# hv_mux_tr_sw.net
KiCad netlist of a schematic drawn in Altium Designer
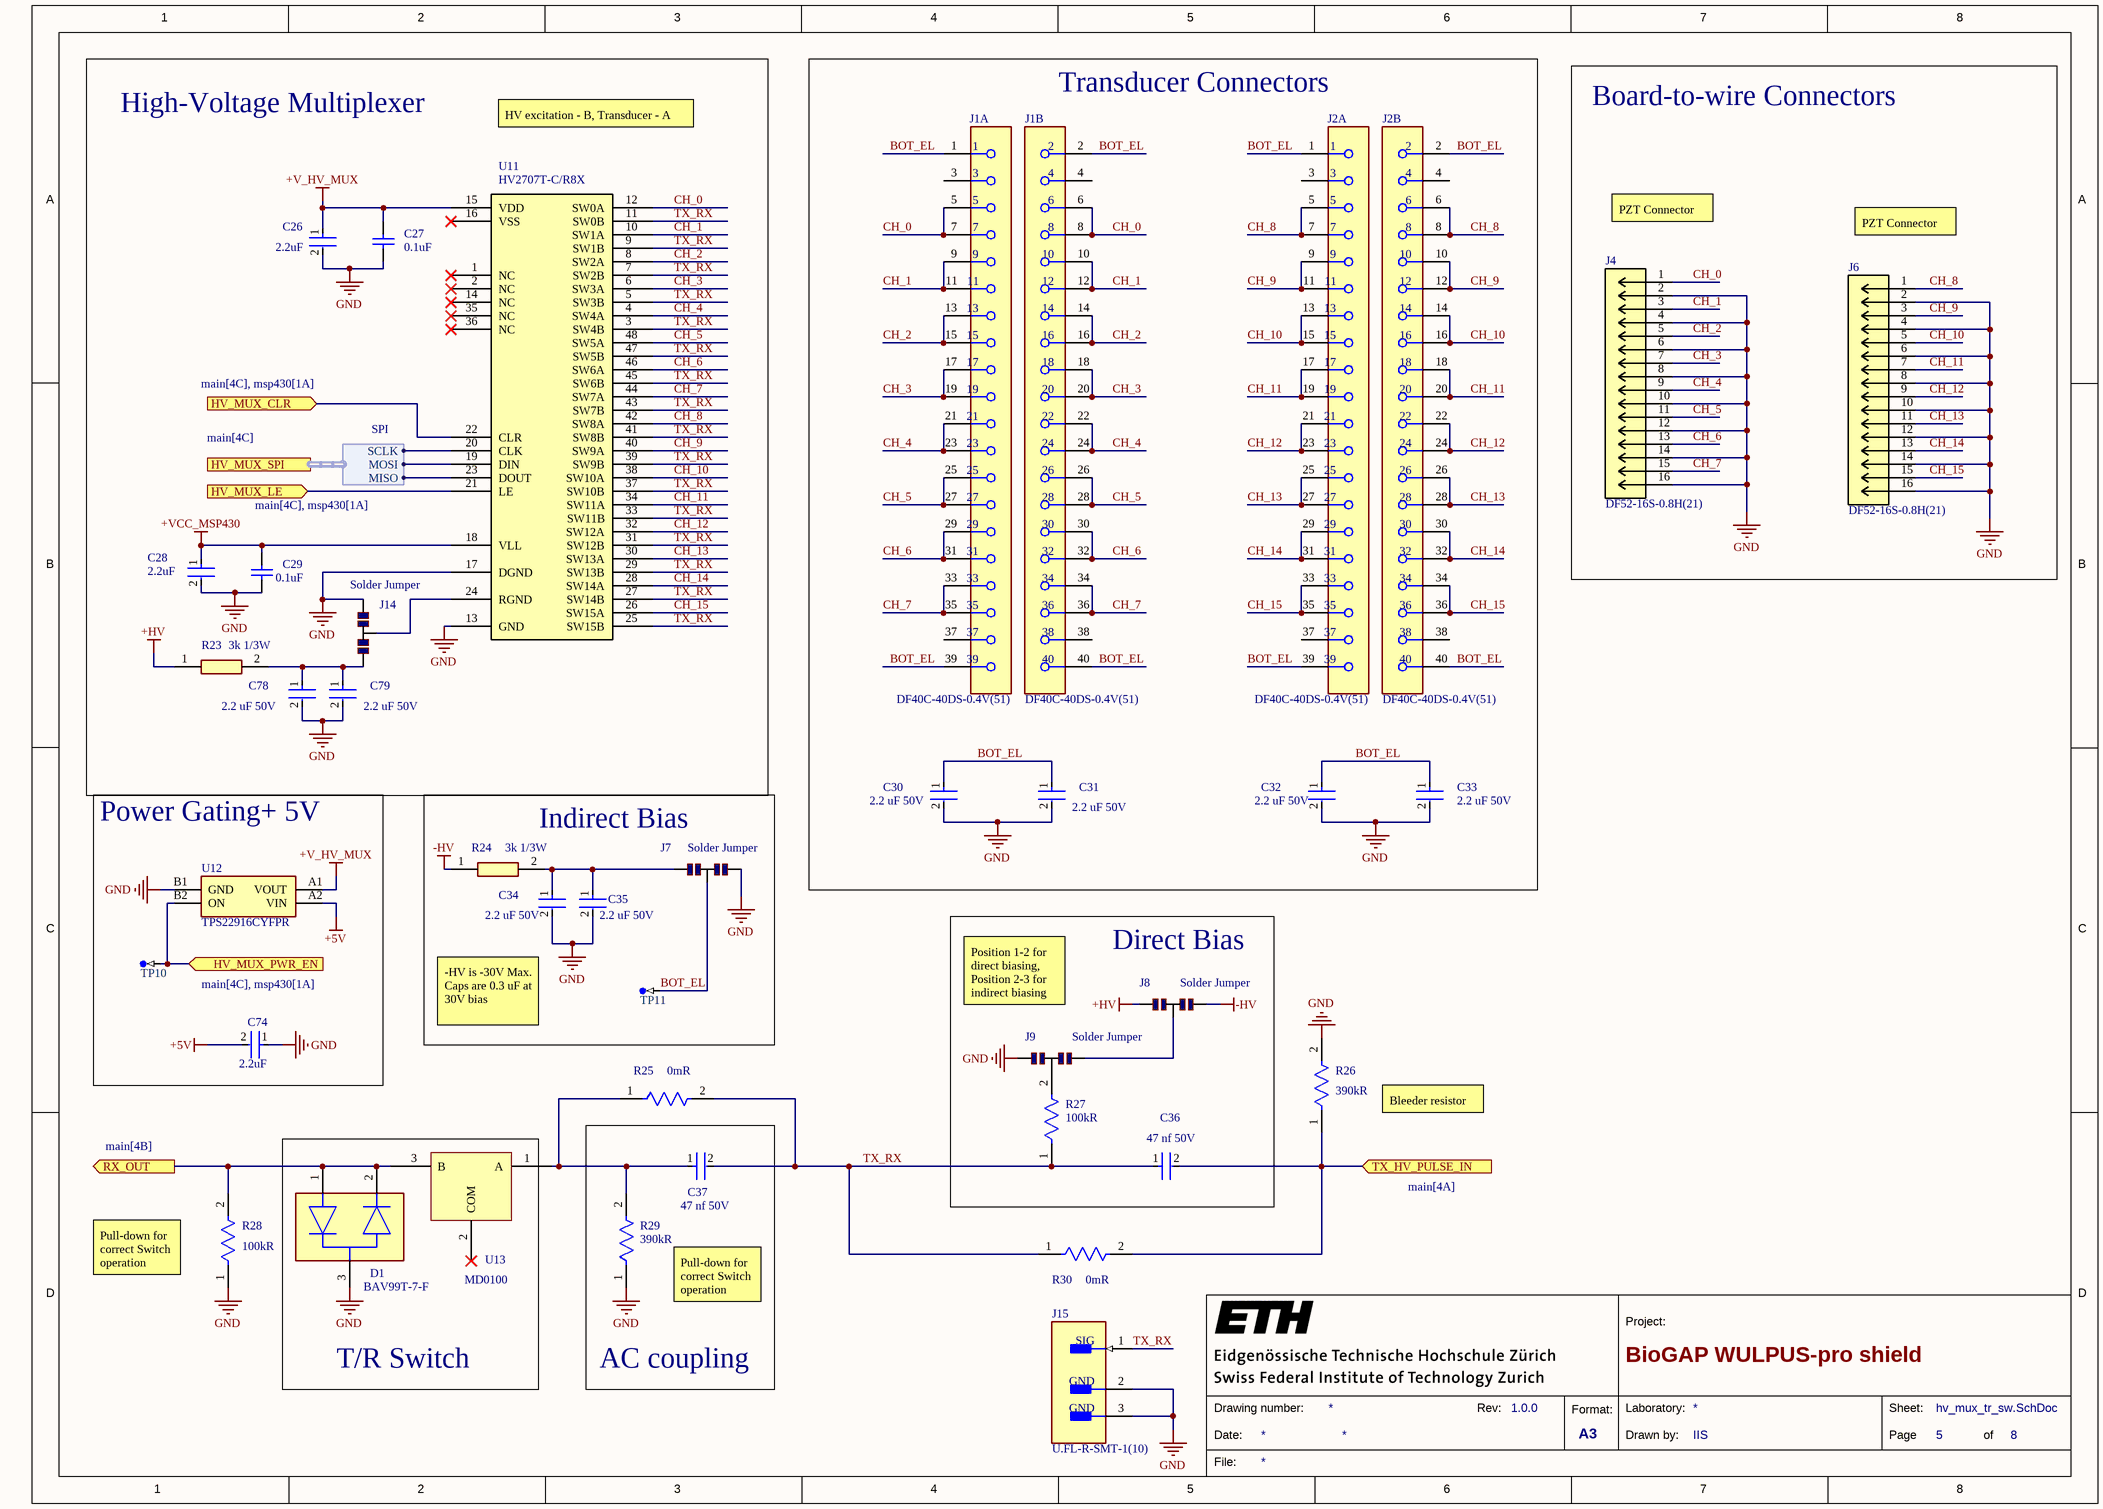
[diagram p0: hv_mux_tr_sw.SchDoc]

(export (version "E")
  (design (tool "Eeschema 10.0.6"))
  (components
    (comp (ref "C26")
      (value "C1005X7S1A225K050BC")
      (footprint "FP-C1005-050-0_15-0_1-MFG")
      (fields (field (name "CAPACITANCE") "2.2uF") (field (name "TOLERANCE") "10%"))
      (libsource (lib "Altium Content Vault") (part "b4654b650e69147ec39a6b967a45e02"))
    )
    (comp (ref "C27")
      (value "C0402C104K4RACTU")
      (footprint "CAPC1005X55X30LL05T10")
      (fields (field (name "MANUFACTURER") "Kemet") (field (name "CAPACITANCE") "0.1uF"))
      (libsource (lib "Altium Content Vault") (part "CAP"))
    )
    (comp (ref "C28")
      (value "C1005X7S1A225K050BC")
      (footprint "FP-C1005-050-0_15-0_1-MFG")
      (fields (field (name "CAPACITANCE") "2.2uF") (field (name "TOLERANCE") "10%"))
      (libsource (lib "Altium Content Vault") (part "b4654b650e69147ec39a6b967a45e02"))
    )
    (comp (ref "C29")
      (value "C0402C104K4RACTU")
      (footprint "CAPC1005X55X30LL05T10")
      (fields (field (name "MANUFACTURER") "Kemet") (field (name "CAPACITANCE") "0.1uF"))
      (libsource (lib "Altium Content Vault") (part "CAP"))
    )
    (comp (ref "C30")
      (value "GRM188R61H225ME11")
      (footprint "FP-GRM188-0_2-IPC_B")
      (fields (field (name "CAPACITANCE") "2.2 uF 50V") (field (name "TOLERANCE") "20%"))
      (libsource (lib "Altium Content Vault") (part "11868f565c42a9108669ba33697ecf6"))
    )
    (comp (ref "C31")
      (value "GRM188R61H225ME11")
      (footprint "FP-GRM188-0_2-IPC_B")
      (fields (field (name "CAPACITANCE") "2.2 uF 50V") (field (name "TOLERANCE") "20%"))
      (libsource (lib "Altium Content Vault") (part "11868f565c42a9108669ba33697ecf6"))
    )
    (comp (ref "C32")
      (value "GRM188R61H225ME11")
      (footprint "FP-GRM188-0_2-IPC_B")
      (fields (field (name "CAPACITANCE") "2.2 uF 50V") (field (name "TOLERANCE") "20%"))
      (libsource (lib "Altium Content Vault") (part "11868f565c42a9108669ba33697ecf6"))
    )
    (comp (ref "C33")
      (value "GRM188R61H225ME11")
      (footprint "FP-GRM188-0_2-IPC_B")
      (fields (field (name "CAPACITANCE") "2.2 uF 50V") (field (name "TOLERANCE") "20%"))
      (libsource (lib "Altium Content Vault") (part "11868f565c42a9108669ba33697ecf6"))
    )
    (comp (ref "C34")
      (value "GRM188R61H225ME11")
      (footprint "FP-GRM188-0_2-IPC_B")
      (fields (field (name "CAPACITANCE") "2.2 uF 50V") (field (name "TOLERANCE") "20%"))
      (libsource (lib "Altium Content Vault") (part "11868f565c42a9108669ba33697ecf6"))
    )
    (comp (ref "C35")
      (value "GRM188R61H225ME11")
      (footprint "FP-GRM188-0_2-IPC_B")
      (fields (field (name "CAPACITANCE") "2.2 uF 50V") (field (name "TOLERANCE") "20%"))
      (libsource (lib "Altium Content Vault") (part "11868f565c42a9108669ba33697ecf6"))
    )
    (comp (ref "C36")
      (value "GRM155R71H473ME14D")
      (footprint "FP-GRM155-0_05-IPC_C")
      (fields (field (name "TOLERANCE") "20%") (field (name "CAPACITANCE") "47 nf 50V"))
      (libsource (lib "Altium Content Vault") (part "02cd4be3c70576c341d710602a673aa"))
    )
    (comp (ref "C37")
      (value "GRM155R71H473ME14D")
      (footprint "FP-GRM155-0_05-IPC_C")
      (fields (field (name "TOLERANCE") "20%") (field (name "CAPACITANCE") "47 nf 50V"))
      (libsource (lib "Altium Content Vault") (part "02cd4be3c70576c341d710602a673aa"))
    )
    (comp (ref "C74")
      (value "C1005X7S1A225K050BC")
      (footprint "FP-C1005-050-0_15-0_1-MFG")
      (fields (field (name "CAPACITANCE") "2.2uF") (field (name "TOLERANCE") "10%"))
      (libsource (lib "Altium Content Vault") (part "b4654b650e69147ec39a6b967a45e02"))
    )
    (comp (ref "C78")
      (value "GRM188R61H225ME11")
      (footprint "FP-GRM188-0_2-IPC_B")
      (fields (field (name "CAPACITANCE") "2.2 uF 50V") (field (name "TOLERANCE") "20%"))
      (libsource (lib "Altium Content Vault") (part "11868f565c42a9108669ba33697ecf6"))
    )
    (comp (ref "C79")
      (value "GRM188R61H225ME11")
      (footprint "FP-GRM188-0_2-IPC_B")
      (fields (field (name "CAPACITANCE") "2.2 uF 50V") (field (name "TOLERANCE") "20%"))
      (libsource (lib "Altium Content Vault") (part "11868f565c42a9108669ba33697ecf6"))
    )
    (comp (ref "D1")
      (value "BAV99T-7-F")
      (footprint "FP-SOT523-MFG")
      (description "DIODE ARRAY GP 85V 75MA SOT523")
      (fields
        (field (name "OCTOPART") "https://octopart.com/bav99t-7-f-diodes+inc.-326340")
        (field (name "MANUFACTURER") "Diodes Inc.")
      )
      (libsource (lib "Altium Content Vault") (part "070e4dda4d860bc04de3109e77921ad"))
    )
    (comp (ref "J1")
      (value "DF40C-40DS-0.4V(51)")
      (footprint "FP-DF40C-40DS-0_4V_51-MFG")
      (description "CONN RCPT 40POS SMD GOLD")
      (fields
        (field (name "MANUFACTURER") "Hirose")
        (field (name "OCTOPART") "https://octopart.com/df40c-40ds-0.4v%2851%29-hirose-19073526")
      )
      (libsource (lib "Altium Content Vault") (part "7acf1c4a8db21028d11741a46a6ec78"))
    )
    (comp (ref "J2")
      (value "DF40C-40DS-0.4V(51)")
      (footprint "FP-DF40C-40DS-0_4V_51-MFG")
      (description "CONN RCPT 40POS SMD GOLD")
      (fields
        (field (name "MANUFACTURER") "Hirose")
        (field (name "OCTOPART") "https://octopart.com/df40c-40ds-0.4v%2851%29-hirose-19073526")
      )
      (libsource (lib "Altium Content Vault") (part "7acf1c4a8db21028d11741a46a6ec78"))
    )
    (comp (ref "J4")
      (value "DF52-16S-0.8H(21)")
      (footprint "CONN_DF52-16S-0.8H(21)_HIR")
      (description "No Description Available")
      (fields (field (name "COPYRIGHT") "Copyright (C) 2022 Ultra Librarian. All rights reserved."))
      (libsource (lib "wulpus_hv") (part "DF52-16S-0.8H(21)"))
    )
    (comp (ref "J6")
      (value "DF52-16S-0.8H(21)")
      (footprint "CONN_DF52-16S-0.8H(21)_HIR")
      (description "No Description Available")
      (fields (field (name "COPYRIGHT") "Copyright (C) 2022 Ultra Librarian. All rights reserved."))
      (libsource (lib "wulpus_hv") (part "DF52-16S-0.8H(21)"))
    )
    (comp (ref "J7")
      (value "Solder Jumper")
      (footprint "Jumper 3 pins")
      (description "Solder Jumper 3 Pads")
      (libsource (lib "ETHZ Vault") (part "Solder Jumper 3-pads"))
    )
    (comp (ref "J8")
      (value "Solder Jumper")
      (footprint "Jumper 3 pins")
      (description "Solder Jumper 3 Pads")
      (libsource (lib "ETHZ Vault") (part "Solder Jumper 3-pads"))
    )
    (comp (ref "J9")
      (value "Solder Jumper")
      (footprint "Jumper 3 pins")
      (description "Solder Jumper 3 Pads")
      (libsource (lib "ETHZ Vault") (part "Solder Jumper 3-pads"))
    )
    (comp (ref "J14")
      (value "Solder Jumper")
      (footprint "Jumper 3 pins")
      (description "Solder Jumper 3 Pads")
      (libsource (lib "wulpus_pro_acq_pcb") (part "CMP-00467-6"))
    )
    (comp (ref "J15")
      (value "U.FL-R-SMT-1(10)")
      (footprint "FP-U_FL-R-SMT-1_10-MFG")
      (description "CONN U.FL RCPT STR 50 OHM SMD")
      (libsource (lib "Altium Content Vault") (part "7158abf7d987fa84906f6fb0d115710"))
    )
    (comp (ref "R23")
      (value "ERJ-PA3J302V")
      (footprint "SamacSys:ERJP03_PA3_(0603)")
      (description "Resistor")
      (fields (field (name "MOUSER PART NUMBER") "667-ERJ-PA3J302V") (field (name "RES") "3k 1/3W"))
      (libsource (lib "*") (part "ERJ-PA3J302V"))
    )
    (comp (ref "R24")
      (value "ERJ-PA3J302V")
      (footprint "SamacSys:ERJP03_PA3_(0603)")
      (fields (field (name "MOUSER PART NUMBER") "667-ERJ-PA3J302V") (field (name "RES") "3k 1/3W"))
      (libsource (lib "*") (part "ERJ-PA3J302V"))
    )
    (comp (ref "R25")
      (value "CRCW04020000Z0ED")
      (footprint "FP-CRCW0402-e3-IPC_C")
      (fields (field (name "TOLERANCE") "5%") (field (name "RESISTANCE") "0mR"))
      (libsource (lib "Altium Content Vault") (part "1029c3af85768c4190bb7ad29bc67b5"))
    )
    (comp (ref "R26")
      (value "RC1005F394CS")
      (footprint "FP-RC1005-MFG")
      (fields (field (name "TOLERANCE") "1%") (field (name "RESISTANCE") "390kR"))
      (libsource (lib "Altium Content Vault") (part "1029c3af85768c4190bb7ad29bc67b5"))
    )
    (comp (ref "R27")
      (value "ERJ-2RKF1003X")
      (footprint "FP-ERJ2RK-IPC_C")
      (fields (field (name "RESISTANCE") "100kR") (field (name "TOLERANCE") "1%"))
      (libsource (lib "Altium Content Vault") (part "1029c3af85768c4190bb7ad29bc67b5"))
    )
    (comp (ref "R28")
      (value "ERJ-2RKF1003X")
      (footprint "FP-ERJ2RK-IPC_C")
      (fields (field (name "RESISTANCE") "100kR") (field (name "TOLERANCE") "1%"))
      (libsource (lib "Altium Content Vault") (part "1029c3af85768c4190bb7ad29bc67b5"))
    )
    (comp (ref "R29")
      (value "RC1005F394CS")
      (footprint "FP-RC1005-MFG")
      (fields (field (name "TOLERANCE") "1%") (field (name "RESISTANCE") "390kR"))
      (libsource (lib "Altium Content Vault") (part "1029c3af85768c4190bb7ad29bc67b5"))
    )
    (comp (ref "R30")
      (value "CRCW04020000Z0ED")
      (footprint "FP-CRCW0402-e3-IPC_C")
      (fields (field (name "TOLERANCE") "5%") (field (name "RESISTANCE") "0mR"))
      (libsource (lib "Altium Content Vault") (part "1029c3af85768c4190bb7ad29bc67b5"))
    )
    (comp (ref "TP10")
      (value "TP-SM-C-100")
      (footprint "TP-SM-C-100")
      (description "Test Point, Surface Mount, Circular, Pad Diameter 1 mm")
      (libsource (lib "wulpus") (part "CMP-0484-00002-1"))
    )
    (comp (ref "TP11")
      (value "TP-SM-C-100")
      (footprint "TP-SM-C-100")
      (description "Test Point, Surface Mount, Circular, Pad Diameter 1 mm")
      (libsource (lib "wulpus") (part "CMP-0484-00002-1"))
    )
    (comp (ref "U11")
      (value "HV2707T-C/R8X")
      (footprint "LQFP48_7X7MC_MCH")
      (description "16-CH 200V No Hv Bias Switch (SPST), 2 Bleed Resistor 48 LQFP 7X7X1.4MM T/r Rohs Compliant: Yes")
      (fields
        (field (name "MANUFACTURER") "Microchip")
        (field (name "MANUFACTURER PART NUMBER") "HV2707T-C/R8X")
      )
      (libsource (lib "wulpus_hv") (part "HV2707T-C/R8X"))
    )
    (comp (ref "U12")
      (value "TPS22916CYFPR")
      (footprint "BGA4C40P2X2_78X78X50")
      (description "TPS22916 5.5-V, 2-A Ultra-Low Leakage Load Switch")
      (libsource (lib "TPS22916CYFPR") (part "TPS22916CYFPR"))
    )
    (comp (ref "U13") (value "MD0100") (footprint "AMP_PHA-1+") (libsource (lib "MD01000") (part "MD0100")))
  )
  (nets
    (net (code "2") (name "+5V") (class "Default")
      (node (ref "C74") (pin "2") (pinfunction "2_2") (pintype "passive"))
      (node (ref "U12") (pin "A2") (pinfunction "VIN_A2") (pintype "passive"))
    )
    (net (code "3") (name "+HV") (class "Default")
      (node (ref "J8") (pin "1") (pinfunction "1_1") (pintype "passive"))
      (node (ref "R23") (pin "1") (pinfunction "1_1") (pintype "passive"))
    )
    (net (code "4") (name "+VCC_MSP430") (class "Default")
      (node (ref "C28") (pin "1") (pinfunction "1_1") (pintype "passive"))
      (node (ref "C29") (pin "2") (pinfunction "2_2") (pintype "passive"))
      (node (ref "U11") (pin "18") (pinfunction "VLL_18") (pintype "passive"))
    )
    (net (code "5") (name "+V_HV_MUX") (class "Default")
      (node (ref "C26") (pin "1") (pinfunction "1_1") (pintype "passive"))
      (node (ref "C27") (pin "2") (pinfunction "2_2") (pintype "passive"))
      (node (ref "U11") (pin "15") (pinfunction "VDD_15") (pintype "passive"))
      (node (ref "U12") (pin "A1") (pinfunction "VOUT_A1") (pintype "passive"))
    )
    (net (code "6") (name "-HV") (class "Default")
      (node (ref "J8") (pin "3") (pinfunction "3_3") (pintype "passive"))
      (node (ref "R24") (pin "1") (pinfunction "1_1") (pintype "passive"))
    )
    (net (code "7") (name "/BOT_EL") (class "Default")
      (node (ref "C30") (pin "1") (pinfunction "1_1") (pintype "passive"))
      (node (ref "C31") (pin "1") (pinfunction "1_1") (pintype "passive"))
      (node (ref "C32") (pin "1") (pinfunction "1_1") (pintype "passive"))
      (node (ref "C33") (pin "1") (pinfunction "1_1") (pintype "passive"))
      (node (ref "J1") (pin "1") (pinfunction "1_1") (pintype "passive"))
      (node (ref "J1") (pin "2") (pinfunction "2_2") (pintype "passive"))
      (node (ref "J1") (pin "39") (pinfunction "39_39") (pintype "passive"))
      (node (ref "J1") (pin "40") (pinfunction "40_40") (pintype "passive"))
      (node (ref "J2") (pin "1") (pinfunction "1_1") (pintype "passive"))
      (node (ref "J2") (pin "2") (pinfunction "2_2") (pintype "passive"))
      (node (ref "J2") (pin "39") (pinfunction "39_39") (pintype "passive"))
      (node (ref "J2") (pin "40") (pinfunction "40_40") (pintype "passive"))
      (node (ref "J7") (pin "2") (pinfunction "2_2") (pintype "passive"))
      (node (ref "TP11") (pin "1") (pinfunction "1_1") (pintype "input"))
    )
    (net (code "8") (name "/CH_0") (class "Default")
      (node (ref "J1") (pin "5") (pinfunction "5_5") (pintype "passive"))
      (node (ref "J1") (pin "6") (pinfunction "6_6") (pintype "passive"))
      (node (ref "J1") (pin "7") (pinfunction "7_7") (pintype "passive"))
      (node (ref "J1") (pin "8") (pinfunction "8_8") (pintype "passive"))
      (node (ref "J4") (pin "1") (pinfunction "1_1") (pintype "passive"))
      (node (ref "U11") (pin "12") (pinfunction "SW0A_12") (pintype "passive"))
    )
    (net (code "9") (name "/CH_1") (class "Default")
      (node (ref "J1") (pin "10") (pinfunction "10_10") (pintype "passive"))
      (node (ref "J1") (pin "11") (pinfunction "11_11") (pintype "passive"))
      (node (ref "J1") (pin "12") (pinfunction "12_12") (pintype "passive"))
      (node (ref "J1") (pin "9") (pinfunction "9_9") (pintype "passive"))
      (node (ref "J4") (pin "3") (pinfunction "3_3") (pintype "passive"))
      (node (ref "U11") (pin "10") (pinfunction "SW1A_10") (pintype "passive"))
    )
    (net (code "10") (name "/CH_2") (class "Default")
      (node (ref "J1") (pin "13") (pinfunction "13_13") (pintype "passive"))
      (node (ref "J1") (pin "14") (pinfunction "14_14") (pintype "passive"))
      (node (ref "J1") (pin "15") (pinfunction "15_15") (pintype "passive"))
      (node (ref "J1") (pin "16") (pinfunction "16_16") (pintype "passive"))
      (node (ref "J4") (pin "5") (pinfunction "5_5") (pintype "passive"))
      (node (ref "U11") (pin "8") (pinfunction "SW2A_8") (pintype "passive"))
    )
    (net (code "11") (name "/CH_3") (class "Default")
      (node (ref "J1") (pin "17") (pinfunction "17_17") (pintype "passive"))
      (node (ref "J1") (pin "18") (pinfunction "18_18") (pintype "passive"))
      (node (ref "J1") (pin "19") (pinfunction "19_19") (pintype "passive"))
      (node (ref "J1") (pin "20") (pinfunction "20_20") (pintype "passive"))
      (node (ref "J4") (pin "7") (pinfunction "7_7") (pintype "passive"))
      (node (ref "U11") (pin "6") (pinfunction "SW3A_6") (pintype "passive"))
    )
    (net (code "12") (name "/CH_4") (class "Default")
      (node (ref "J1") (pin "21") (pinfunction "21_21") (pintype "passive"))
      (node (ref "J1") (pin "22") (pinfunction "22_22") (pintype "passive"))
      (node (ref "J1") (pin "23") (pinfunction "23_23") (pintype "passive"))
      (node (ref "J1") (pin "24") (pinfunction "24_24") (pintype "passive"))
      (node (ref "J4") (pin "9") (pinfunction "9_9") (pintype "passive"))
      (node (ref "U11") (pin "4") (pinfunction "SW4A_4") (pintype "passive"))
    )
    (net (code "13") (name "/CH_5") (class "Default")
      (node (ref "J1") (pin "25") (pinfunction "25_25") (pintype "passive"))
      (node (ref "J1") (pin "26") (pinfunction "26_26") (pintype "passive"))
      (node (ref "J1") (pin "27") (pinfunction "27_27") (pintype "passive"))
      (node (ref "J1") (pin "28") (pinfunction "28_28") (pintype "passive"))
      (node (ref "J4") (pin "11") (pinfunction "11_11") (pintype "passive"))
      (node (ref "U11") (pin "48") (pinfunction "SW5A_48") (pintype "passive"))
    )
    (net (code "14") (name "/CH_6") (class "Default")
      (node (ref "J1") (pin "29") (pinfunction "29_29") (pintype "passive"))
      (node (ref "J1") (pin "30") (pinfunction "30_30") (pintype "passive"))
      (node (ref "J1") (pin "31") (pinfunction "31_31") (pintype "passive"))
      (node (ref "J1") (pin "32") (pinfunction "32_32") (pintype "passive"))
      (node (ref "J4") (pin "13") (pinfunction "13_13") (pintype "passive"))
      (node (ref "U11") (pin "46") (pinfunction "SW6A_46") (pintype "passive"))
    )
    (net (code "15") (name "/CH_7") (class "Default")
      (node (ref "J1") (pin "33") (pinfunction "33_33") (pintype "passive"))
      (node (ref "J1") (pin "34") (pinfunction "34_34") (pintype "passive"))
      (node (ref "J1") (pin "35") (pinfunction "35_35") (pintype "passive"))
      (node (ref "J1") (pin "36") (pinfunction "36_36") (pintype "passive"))
      (node (ref "J4") (pin "15") (pinfunction "15_15") (pintype "passive"))
      (node (ref "U11") (pin "44") (pinfunction "SW7A_44") (pintype "passive"))
    )
    (net (code "16") (name "/CH_8") (class "Default")
      (node (ref "J2") (pin "5") (pinfunction "5_5") (pintype "passive"))
      (node (ref "J2") (pin "6") (pinfunction "6_6") (pintype "passive"))
      (node (ref "J2") (pin "7") (pinfunction "7_7") (pintype "passive"))
      (node (ref "J2") (pin "8") (pinfunction "8_8") (pintype "passive"))
      (node (ref "J6") (pin "1") (pinfunction "1_1") (pintype "passive"))
      (node (ref "U11") (pin "42") (pinfunction "SW8A_42") (pintype "passive"))
    )
    (net (code "17") (name "/CH_9") (class "Default")
      (node (ref "J2") (pin "10") (pinfunction "10_10") (pintype "passive"))
      (node (ref "J2") (pin "11") (pinfunction "11_11") (pintype "passive"))
      (node (ref "J2") (pin "12") (pinfunction "12_12") (pintype "passive"))
      (node (ref "J2") (pin "9") (pinfunction "9_9") (pintype "passive"))
      (node (ref "J6") (pin "3") (pinfunction "3_3") (pintype "passive"))
      (node (ref "U11") (pin "40") (pinfunction "SW9A_40") (pintype "passive"))
    )
    (net (code "18") (name "/CH_10") (class "Default")
      (node (ref "J2") (pin "13") (pinfunction "13_13") (pintype "passive"))
      (node (ref "J2") (pin "14") (pinfunction "14_14") (pintype "passive"))
      (node (ref "J2") (pin "15") (pinfunction "15_15") (pintype "passive"))
      (node (ref "J2") (pin "16") (pinfunction "16_16") (pintype "passive"))
      (node (ref "J6") (pin "5") (pinfunction "5_5") (pintype "passive"))
      (node (ref "U11") (pin "38") (pinfunction "SW10A_38") (pintype "passive"))
    )
    (net (code "19") (name "/CH_11") (class "Default")
      (node (ref "J2") (pin "17") (pinfunction "17_17") (pintype "passive"))
      (node (ref "J2") (pin "18") (pinfunction "18_18") (pintype "passive"))
      (node (ref "J2") (pin "19") (pinfunction "19_19") (pintype "passive"))
      (node (ref "J2") (pin "20") (pinfunction "20_20") (pintype "passive"))
      (node (ref "J6") (pin "7") (pinfunction "7_7") (pintype "passive"))
      (node (ref "U11") (pin "34") (pinfunction "SW11A_34") (pintype "passive"))
    )
    (net (code "20") (name "/CH_12") (class "Default")
      (node (ref "J2") (pin "21") (pinfunction "21_21") (pintype "passive"))
      (node (ref "J2") (pin "22") (pinfunction "22_22") (pintype "passive"))
      (node (ref "J2") (pin "23") (pinfunction "23_23") (pintype "passive"))
      (node (ref "J2") (pin "24") (pinfunction "24_24") (pintype "passive"))
      (node (ref "J6") (pin "9") (pinfunction "9_9") (pintype "passive"))
      (node (ref "U11") (pin "32") (pinfunction "SW12A_32") (pintype "passive"))
    )
    (net (code "21") (name "/CH_13") (class "Default")
      (node (ref "J2") (pin "25") (pinfunction "25_25") (pintype "passive"))
      (node (ref "J2") (pin "26") (pinfunction "26_26") (pintype "passive"))
      (node (ref "J2") (pin "27") (pinfunction "27_27") (pintype "passive"))
      (node (ref "J2") (pin "28") (pinfunction "28_28") (pintype "passive"))
      (node (ref "J6") (pin "11") (pinfunction "11_11") (pintype "passive"))
      (node (ref "U11") (pin "30") (pinfunction "SW13A_30") (pintype "passive"))
    )
    (net (code "22") (name "/CH_14") (class "Default")
      (node (ref "J2") (pin "29") (pinfunction "29_29") (pintype "passive"))
      (node (ref "J2") (pin "30") (pinfunction "30_30") (pintype "passive"))
      (node (ref "J2") (pin "31") (pinfunction "31_31") (pintype "passive"))
      (node (ref "J2") (pin "32") (pinfunction "32_32") (pintype "passive"))
      (node (ref "J6") (pin "13") (pinfunction "13_13") (pintype "passive"))
      (node (ref "U11") (pin "28") (pinfunction "SW14A_28") (pintype "passive"))
    )
    (net (code "23") (name "/CH_15") (class "Default")
      (node (ref "J2") (pin "33") (pinfunction "33_33") (pintype "passive"))
      (node (ref "J2") (pin "34") (pinfunction "34_34") (pintype "passive"))
      (node (ref "J2") (pin "35") (pinfunction "35_35") (pintype "passive"))
      (node (ref "J2") (pin "36") (pinfunction "36_36") (pintype "passive"))
      (node (ref "J6") (pin "15") (pinfunction "15_15") (pintype "passive"))
      (node (ref "U11") (pin "26") (pinfunction "SW15A_26") (pintype "passive"))
    )
    (net (code "24") (name "/HV_MUX_CLR") (class "Default")
      (node (ref "U11") (pin "22") (pinfunction "CLR_22") (pintype "passive"))
    )
    (net (code "25") (name "/HV_MUX_LE") (class "Default")
      (node (ref "U11") (pin "21") (pinfunction "LE_21") (pintype "passive"))
    )
    (net (code "26") (name "/HV_MUX_PWR_EN") (class "Default")
      (node (ref "TP10") (pin "1") (pinfunction "1_1") (pintype "input"))
      (node (ref "U12") (pin "B2") (pinfunction "ON_B2") (pintype "passive"))
    )
    (net (code "27") (name "/MISO") (class "Default")
      (node (ref "U11") (pin "23") (pinfunction "DOUT_23") (pintype "passive"))
    )
    (net (code "28") (name "/MOSI") (class "Default")
      (node (ref "U11") (pin "19") (pinfunction "DIN_19") (pintype "passive"))
    )
    (net (code "29") (name "/RX_OUT") (class "Default")
      (node (ref "D1") (pin "1") (pinfunction "1_1") (pintype "passive"))
      (node (ref "D1") (pin "2") (pinfunction "2_2") (pintype "passive"))
      (node (ref "R28") (pin "2") (pinfunction "2_2") (pintype "passive"))
      (node (ref "U13") (pin "3") (pinfunction "B_3") (pintype "passive"))
    )
    (net (code "30") (name "/SCLK") (class "Default")
      (node (ref "U11") (pin "20") (pinfunction "CLK_20") (pintype "passive"))
    )
    (net (code "31") (name "/TX_HV_PULSE_IN") (class "Default")
      (node (ref "C36") (pin "2") (pinfunction "2_2") (pintype "passive"))
      (node (ref "R26") (pin "1") (pinfunction "1_1") (pintype "passive"))
      (node (ref "R30") (pin "2") (pinfunction "2_2") (pintype "passive"))
    )
    (net (code "32") (name "/TX_RX") (class "Default")
      (node (ref "C36") (pin "1") (pinfunction "1_1") (pintype "passive"))
      (node (ref "C37") (pin "2") (pinfunction "2_2") (pintype "passive"))
      (node (ref "J15") (pin "1") (pinfunction "SIG_1") (pintype "input"))
      (node (ref "R25") (pin "2") (pinfunction "2_2") (pintype "passive"))
      (node (ref "R27") (pin "1") (pinfunction "1_1") (pintype "passive"))
      (node (ref "R30") (pin "1") (pinfunction "1_1") (pintype "passive"))
      (node (ref "U11") (pin "11") (pinfunction "SW0B_11") (pintype "passive"))
      (node (ref "U11") (pin "25") (pinfunction "SW15B_25") (pintype "passive"))
      (node (ref "U11") (pin "27") (pinfunction "SW14B_27") (pintype "passive"))
      (node (ref "U11") (pin "29") (pinfunction "SW13B_29") (pintype "passive"))
      (node (ref "U11") (pin "3") (pinfunction "SW4B_3") (pintype "passive"))
      (node (ref "U11") (pin "31") (pinfunction "SW12B_31") (pintype "passive"))
      (node (ref "U11") (pin "33") (pinfunction "SW11B_33") (pintype "passive"))
      (node (ref "U11") (pin "37") (pinfunction "SW10B_37") (pintype "passive"))
      (node (ref "U11") (pin "39") (pinfunction "SW9B_39") (pintype "passive"))
      (node (ref "U11") (pin "41") (pinfunction "SW8B_41") (pintype "passive"))
      (node (ref "U11") (pin "43") (pinfunction "SW7B_43") (pintype "passive"))
      (node (ref "U11") (pin "45") (pinfunction "SW6B_45") (pintype "passive"))
      (node (ref "U11") (pin "47") (pinfunction "SW5B_47") (pintype "passive"))
      (node (ref "U11") (pin "5") (pinfunction "SW3B_5") (pintype "passive"))
      (node (ref "U11") (pin "7") (pinfunction "SW2B_7") (pintype "passive"))
      (node (ref "U11") (pin "9") (pinfunction "SW1B_9") (pintype "passive"))
    )
    (net (code "34") (name "GND") (class "Default")
      (node (ref "C26") (pin "2") (pinfunction "2_2") (pintype "passive"))
      (node (ref "C27") (pin "1") (pinfunction "1_1") (pintype "passive"))
      (node (ref "C28") (pin "2") (pinfunction "2_2") (pintype "passive"))
      (node (ref "C29") (pin "1") (pinfunction "1_1") (pintype "passive"))
      (node (ref "C30") (pin "2") (pinfunction "2_2") (pintype "passive"))
      (node (ref "C31") (pin "2") (pinfunction "2_2") (pintype "passive"))
      (node (ref "C32") (pin "2") (pinfunction "2_2") (pintype "passive"))
      (node (ref "C33") (pin "2") (pinfunction "2_2") (pintype "passive"))
      (node (ref "C34") (pin "2") (pinfunction "2_2") (pintype "passive"))
      (node (ref "C35") (pin "2") (pinfunction "2_2") (pintype "passive"))
      (node (ref "C74") (pin "1") (pinfunction "1_1") (pintype "passive"))
      (node (ref "C78") (pin "2") (pinfunction "2_2") (pintype "passive"))
      (node (ref "C79") (pin "2") (pinfunction "2_2") (pintype "passive"))
      (node (ref "D1") (pin "3") (pinfunction "3_3") (pintype "passive"))
      (node (ref "J14") (pin "3") (pinfunction "3_3") (pintype "passive"))
      (node (ref "J15") (pin "2") (pinfunction "GND_2") (pintype "power_in"))
      (node (ref "J15") (pin "3") (pinfunction "GND_3") (pintype "power_in"))
      (node (ref "J4") (pin "10") (pinfunction "10_10") (pintype "passive"))
      (node (ref "J4") (pin "12") (pinfunction "12_12") (pintype "passive"))
      (node (ref "J4") (pin "14") (pinfunction "14_14") (pintype "passive"))
      (node (ref "J4") (pin "16") (pinfunction "16_16") (pintype "passive"))
      (node (ref "J4") (pin "2") (pinfunction "2_2") (pintype "passive"))
      (node (ref "J4") (pin "4") (pinfunction "4_4") (pintype "passive"))
      (node (ref "J4") (pin "6") (pinfunction "6_6") (pintype "passive"))
      (node (ref "J4") (pin "8") (pinfunction "8_8") (pintype "passive"))
      (node (ref "J6") (pin "10") (pinfunction "10_10") (pintype "passive"))
      (node (ref "J6") (pin "12") (pinfunction "12_12") (pintype "passive"))
      (node (ref "J6") (pin "14") (pinfunction "14_14") (pintype "passive"))
      (node (ref "J6") (pin "16") (pinfunction "16_16") (pintype "passive"))
      (node (ref "J6") (pin "2") (pinfunction "2_2") (pintype "passive"))
      (node (ref "J6") (pin "4") (pinfunction "4_4") (pintype "passive"))
      (node (ref "J6") (pin "6") (pinfunction "6_6") (pintype "passive"))
      (node (ref "J6") (pin "8") (pinfunction "8_8") (pintype "passive"))
      (node (ref "J7") (pin "3") (pinfunction "3_3") (pintype "passive"))
      (node (ref "J9") (pin "1") (pinfunction "1_1") (pintype "passive"))
      (node (ref "R26") (pin "2") (pinfunction "2_2") (pintype "passive"))
      (node (ref "R28") (pin "1") (pinfunction "1_1") (pintype "passive"))
      (node (ref "R29") (pin "1") (pinfunction "1_1") (pintype "passive"))
      (node (ref "U11") (pin "13") (pinfunction "GND_13") (pintype "passive"))
      (node (ref "U11") (pin "17") (pinfunction "DGND_17") (pintype "passive"))
      (node (ref "U12") (pin "B1") (pinfunction "GND_B1") (pintype "passive"))
    )
    (net (code "35") (name "Net-(C34-Pad1)") (class "Default")
      (node (ref "C34") (pin "1") (pinfunction "1_1") (pintype "passive"))
      (node (ref "C35") (pin "1") (pinfunction "1_1") (pintype "passive"))
      (node (ref "J7") (pin "1") (pinfunction "1_1") (pintype "passive"))
      (node (ref "R24") (pin "2") (pinfunction "2_2") (pintype "passive"))
    )
    (net (code "36") (name "Net-(C78-Pad1)") (class "Default")
      (node (ref "C78") (pin "1") (pinfunction "1_1") (pintype "passive"))
      (node (ref "C79") (pin "1") (pinfunction "1_1") (pintype "passive"))
      (node (ref "J14") (pin "1") (pinfunction "1_1") (pintype "passive"))
      (node (ref "R23") (pin "2") (pinfunction "2_2") (pintype "passive"))
    )
    (net (code "37") (name "Net-(J8-Pad2)") (class "Default")
      (node (ref "J8") (pin "2") (pinfunction "2_2") (pintype "passive"))
      (node (ref "J9") (pin "3") (pinfunction "3_3") (pintype "passive"))
    )
    (net (code "38") (name "Net-(J9-Pad2)") (class "Default")
      (node (ref "J9") (pin "2") (pinfunction "2_2") (pintype "passive"))
      (node (ref "R27") (pin "2") (pinfunction "2_2") (pintype "passive"))
    )
    (net (code "39") (name "Net-(U11-RGND)") (class "Default")
      (node (ref "J14") (pin "2") (pinfunction "2_2") (pintype "passive"))
      (node (ref "U11") (pin "24") (pinfunction "RGND_24") (pintype "passive"))
    )
    (net (code "40") (name "Net-(U13-A)") (class "Default")
      (node (ref "C37") (pin "1") (pinfunction "1_1") (pintype "passive"))
      (node (ref "R25") (pin "1") (pinfunction "1_1") (pintype "passive"))
      (node (ref "R29") (pin "2") (pinfunction "2_2") (pintype "passive"))
      (node (ref "U13") (pin "1") (pinfunction "A_1") (pintype "passive"))
    )
    (net (code "41") (name "unconnected-(J1-Pad3)") (class "Default")
      (node (ref "J1") (pin "3") (pinfunction "3_3") (pintype "passive"))
    )
    (net (code "42") (name "unconnected-(J1-Pad4)") (class "Default")
      (node (ref "J1") (pin "4") (pinfunction "4_4") (pintype "passive"))
    )
    (net (code "43") (name "unconnected-(J1-Pad37)") (class "Default")
      (node (ref "J1") (pin "37") (pinfunction "37_37") (pintype "passive"))
    )
    (net (code "44") (name "unconnected-(J1-Pad38)") (class "Default")
      (node (ref "J1") (pin "38") (pinfunction "38_38") (pintype "passive"))
    )
    (net (code "45") (name "unconnected-(J2-Pad3)") (class "Default")
      (node (ref "J2") (pin "3") (pinfunction "3_3") (pintype "passive"))
    )
    (net (code "46") (name "unconnected-(J2-Pad4)") (class "Default")
      (node (ref "J2") (pin "4") (pinfunction "4_4") (pintype "passive"))
    )
    (net (code "47") (name "unconnected-(J2-Pad37)") (class "Default")
      (node (ref "J2") (pin "37") (pinfunction "37_37") (pintype "passive"))
    )
    (net (code "48") (name "unconnected-(J2-Pad38)") (class "Default")
      (node (ref "J2") (pin "38") (pinfunction "38_38") (pintype "passive"))
    )
    (net (code "49") (name "unconnected-(U11-NC-Pad1)") (class "Default")
      (node (ref "U11") (pin "1") (pinfunction "NC_1") (pintype "passive+no_connect"))
    )
    (net (code "50") (name "unconnected-(U11-NC-Pad2)") (class "Default")
      (node (ref "U11") (pin "2") (pinfunction "NC_2") (pintype "passive+no_connect"))
    )
    (net (code "51") (name "unconnected-(U11-NC-Pad14)") (class "Default")
      (node (ref "U11") (pin "14") (pinfunction "NC_14") (pintype "passive+no_connect"))
    )
    (net (code "52") (name "unconnected-(U11-NC-Pad35)") (class "Default")
      (node (ref "U11") (pin "35") (pinfunction "NC_35") (pintype "passive+no_connect"))
    )
    (net (code "53") (name "unconnected-(U11-NC-Pad36)") (class "Default")
      (node (ref "U11") (pin "36") (pinfunction "NC_36") (pintype "passive+no_connect"))
    )
    (net (code "54") (name "unconnected-(U11-VSS-Pad16)") (class "Default")
      (node (ref "U11") (pin "16") (pinfunction "VSS_16") (pintype "passive+no_connect"))
    )
    (net (code "55") (name "unconnected-(U13-COM-Pad2)") (class "Default")
      (node (ref "U13") (pin "2") (pinfunction "COM_2") (pintype "passive+no_connect"))
    )
  )
)
